# thermostable_constant_current_source.net
KiCad netlist of a schematic drawn in Altium Designer
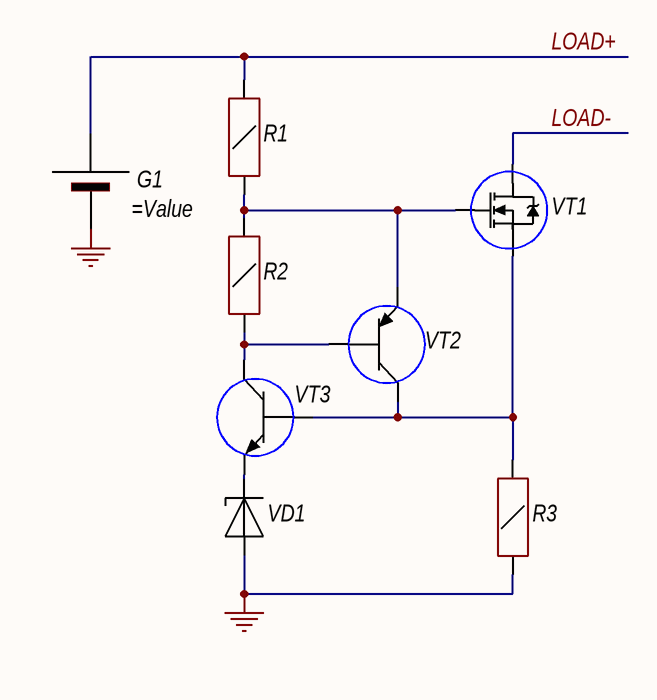
[diagram p0: thermostable_constant_current_source.SchDoc]

(export (version "E")
  (design (tool "Eeschema 10.0.6"))
  (components
    (comp (ref "G1") (value "~") (footprint "18650 1PCS") (libsource (lib "Discrete") (part "Battery")))
    (comp (ref "R1") (value "10к") (footprint "CH1206R") (libsource (lib "Discrete") (part "Resistor")))
    (comp (ref "R2") (value "10к") (footprint "CH1206R") (libsource (lib "Discrete") (part "Resistor")))
    (comp (ref "R3") (value "68") (footprint "CH1206R") (libsource (lib "Discrete") (part "Resistor")))
    (comp (ref "VD1") (value "BZV55C7V5") (footprint "SOD80") (libsource (lib "Diods") (part "Diod Zener")))
    (comp (ref "VT1")
      (value "*")
      (footprint "DPAK")
      (description "Mosfet")
      (libsource (lib "Transistor") (part "N-chanel"))
    )
    (comp (ref "VT2")
      (value "BC857")
      (footprint "standard:SOT23_123")
      (description "Bipolar")
      (libsource (lib "Transistor") (part "PNP"))
    )
    (comp (ref "VT3")
      (value "BC847")
      (footprint "SOT23_123")
      (description "Bipolar")
      (libsource (lib "Transistor") (part "NPN"))
    )
  )
  (nets
    (net (code "1") (name "/LOAD+") (class "Default")
      (node (ref "G1") (pin "1") (pinfunction "Positive_1") (pintype "passive"))
      (node (ref "R1") (pin "2") (pinfunction "2_2") (pintype "passive"))
    )
    (net (code "2") (name "/LOAD-") (class "Default")
      (node (ref "VT1") (pin "2") (pinfunction "D_2") (pintype "passive"))
    )
    (net (code "3") (name "GND") (class "Default")
      (node (ref "G1") (pin "2") (pinfunction "Negative_2") (pintype "passive"))
      (node (ref "R3") (pin "1") (pinfunction "1_1") (pintype "passive"))
      (node (ref "VD1") (pin "1") (pinfunction "A_1") (pintype "passive"))
    )
    (net (code "4") (name "Net-(VD1-C)") (class "Default")
      (node (ref "VD1") (pin "2") (pinfunction "C_2") (pintype "passive"))
      (node (ref "VT3") (pin "3") (pinfunction "E_3") (pintype "passive"))
    )
    (net (code "5") (name "Net-(VT1-G)") (class "Default")
      (node (ref "R1") (pin "1") (pinfunction "1_1") (pintype "passive"))
      (node (ref "R2") (pin "2") (pinfunction "2_2") (pintype "passive"))
      (node (ref "VT1") (pin "1") (pinfunction "G_1") (pintype "passive"))
      (node (ref "VT2") (pin "2") (pinfunction "C_2") (pintype "passive"))
    )
    (net (code "6") (name "Net-(VT1-S)") (class "Default")
      (node (ref "R3") (pin "2") (pinfunction "2_2") (pintype "passive"))
      (node (ref "VT1") (pin "3") (pinfunction "S_3") (pintype "passive"))
      (node (ref "VT2") (pin "3") (pinfunction "E_3") (pintype "passive"))
      (node (ref "VT3") (pin "1") (pinfunction "B_1") (pintype "passive"))
    )
    (net (code "7") (name "Net-(VT2-B)") (class "Default")
      (node (ref "R2") (pin "1") (pinfunction "1_1") (pintype "passive"))
      (node (ref "VT2") (pin "1") (pinfunction "B_1") (pintype "passive"))
      (node (ref "VT3") (pin "2") (pinfunction "C_2") (pintype "passive"))
    )
  )
)
